# untitled.net
KiCad netlist of a schematic drawn in EAGLE
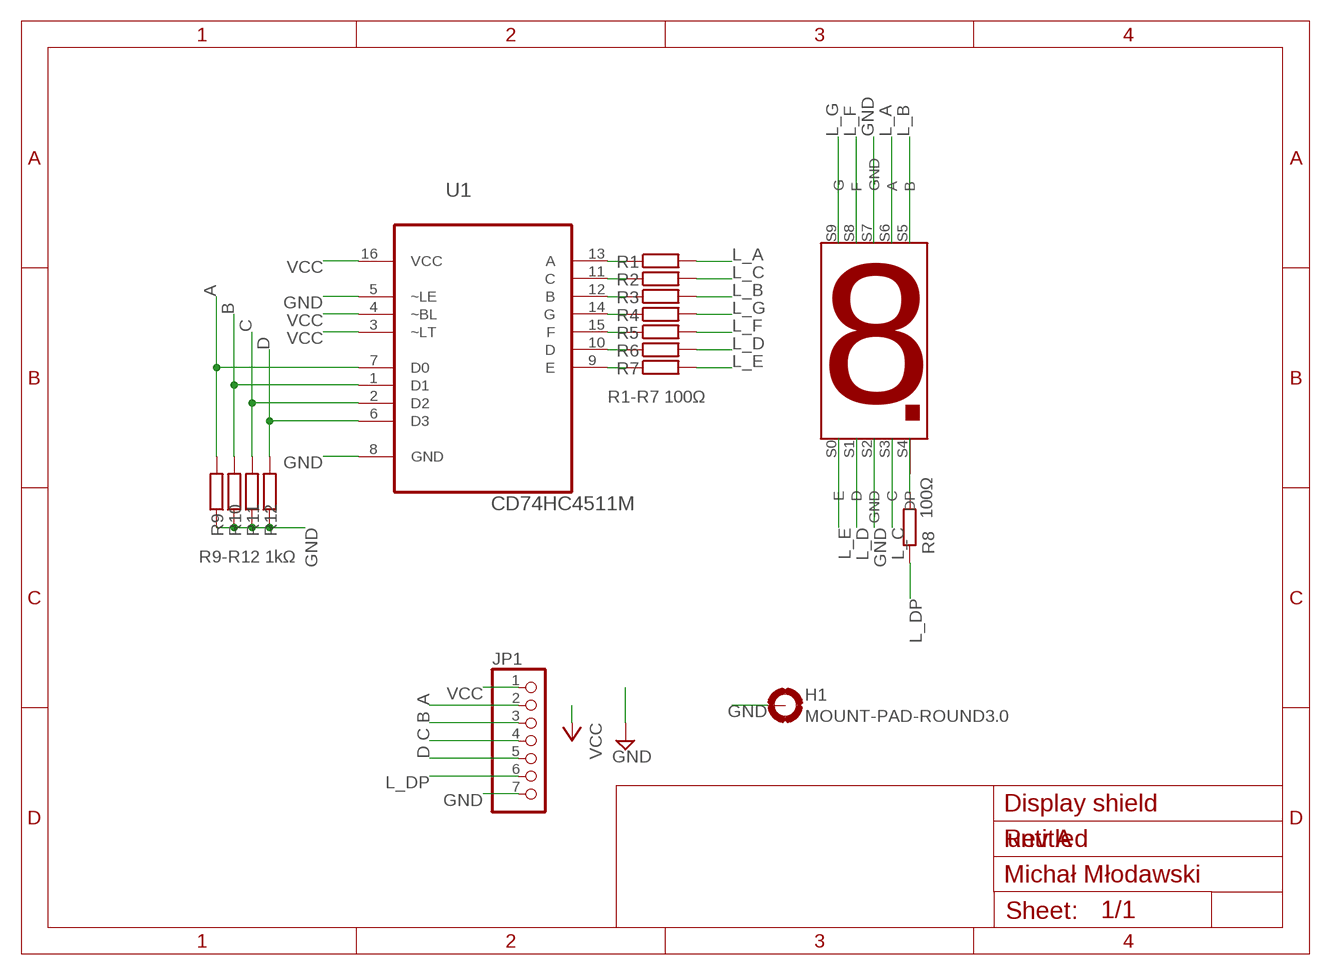
[diagram p0: schematic, sheet 1]

(export (version "E")
  (design (tool "Eeschema 10.0.6"))
  (components
    (comp (ref "H1")
      (value "MOUNT-PAD-ROUND3.0")
      (footprint "eagle-import:3,0-PAD")
      (libsource (lib "eagle-import") (part "MOUNT-PAD-ROUND3.0"))
    )
    (comp (ref "JP1")
      (value "PINHD-1X7")
      (footprint "eagle-import:1X07")
      (libsource (lib "eagle-import") (part "PINHD-1X7"))
    )
    (comp (ref "R1")
      (value "R-EU_R1206")
      (footprint "eagle-import:R1206")
      (libsource (lib "eagle-import") (part "R-EU_R1206"))
    )
    (comp (ref "R2")
      (value "R-EU_R1206")
      (footprint "eagle-import:R1206")
      (libsource (lib "eagle-import") (part "R-EU_R1206"))
    )
    (comp (ref "R3")
      (value "R-EU_R1206")
      (footprint "eagle-import:R1206")
      (libsource (lib "eagle-import") (part "R-EU_R1206"))
    )
    (comp (ref "R4")
      (value "R-EU_R1206")
      (footprint "eagle-import:R1206")
      (libsource (lib "eagle-import") (part "R-EU_R1206"))
    )
    (comp (ref "R5")
      (value "R-EU_R1206")
      (footprint "eagle-import:R1206")
      (libsource (lib "eagle-import") (part "R-EU_R1206"))
    )
    (comp (ref "R6")
      (value "R-EU_R1206")
      (footprint "eagle-import:R1206")
      (libsource (lib "eagle-import") (part "R-EU_R1206"))
    )
    (comp (ref "R7")
      (value "R-EU_R1206")
      (footprint "eagle-import:R1206")
      (libsource (lib "eagle-import") (part "R-EU_R1206"))
    )
    (comp (ref "R8")
      (value "100Ω")
      (footprint "eagle-import:R1206")
      (libsource (lib "eagle-import") (part "R-EU_R1206"))
    )
    (comp (ref "R9")
      (value "R-EU_R1206")
      (footprint "eagle-import:R1206")
      (libsource (lib "eagle-import") (part "R-EU_R1206"))
    )
    (comp (ref "R10")
      (value "R-EU_R1206")
      (footprint "eagle-import:R1206")
      (libsource (lib "eagle-import") (part "R-EU_R1206"))
    )
    (comp (ref "R11")
      (value "R-EU_R1206")
      (footprint "eagle-import:R1206")
      (libsource (lib "eagle-import") (part "R-EU_R1206"))
    )
    (comp (ref "R12")
      (value "R-EU_R1206")
      (footprint "eagle-import:R1206")
      (libsource (lib "eagle-import") (part "R-EU_R1206"))
    )
    (comp (ref "U$1")
      (value "7-SEGMENT-DISPLAY")
      (footprint "eagle-import:7-SEGMENTDISPLAY")
      (libsource (lib "eagle-import") (part "7-SEGMENT-DISPLAY"))
    )
    (comp (ref "U1")
      (value "CD74HC4511M")
      (footprint "eagle-import:SOIC127P600X175-16N")
      (fields (field (name "MF") "Texas Instruments"))
      (libsource (lib "eagle-import") (part "CD74HC4511M"))
    )
  )
  (nets
    (net (code "1") (name "/A") (class "Default")
      (node (ref "JP1") (pin "2") (pinfunction "2_2") (pintype "passive"))
      (node (ref "R9") (pin "2") (pinfunction "2_2") (pintype "passive"))
      (node (ref "U1") (pin "7") (pinfunction "D0_7") (pintype "input"))
    )
    (net (code "2") (name "/B") (class "Default")
      (node (ref "JP1") (pin "3") (pinfunction "3_3") (pintype "passive"))
      (node (ref "R10") (pin "2") (pinfunction "2_2") (pintype "passive"))
      (node (ref "U1") (pin "1") (pinfunction "D1_1") (pintype "input"))
    )
    (net (code "3") (name "/C") (class "Default")
      (node (ref "JP1") (pin "4") (pinfunction "4_4") (pintype "passive"))
      (node (ref "R11") (pin "2") (pinfunction "2_2") (pintype "passive"))
      (node (ref "U1") (pin "2") (pinfunction "D2_2") (pintype "input"))
    )
    (net (code "4") (name "/D") (class "Default")
      (node (ref "JP1") (pin "5") (pinfunction "5_5") (pintype "passive"))
      (node (ref "R12") (pin "2") (pinfunction "2_2") (pintype "passive"))
      (node (ref "U1") (pin "6") (pinfunction "D3_6") (pintype "input"))
    )
    (net (code "5") (name "/L_A") (class "Default")
      (node (ref "R1") (pin "2") (pinfunction "2_2") (pintype "passive"))
      (node (ref "U$1") (pin "S6") (pinfunction "A_S6") (pintype "input"))
    )
    (net (code "6") (name "/L_B") (class "Default")
      (node (ref "R3") (pin "2") (pinfunction "2_2") (pintype "passive"))
      (node (ref "U$1") (pin "S5") (pinfunction "B_S5") (pintype "input"))
    )
    (net (code "7") (name "/L_C") (class "Default")
      (node (ref "R2") (pin "2") (pinfunction "2_2") (pintype "passive"))
      (node (ref "U$1") (pin "S3") (pinfunction "C_S3") (pintype "input"))
    )
    (net (code "8") (name "/L_D") (class "Default")
      (node (ref "R6") (pin "2") (pinfunction "2_2") (pintype "passive"))
      (node (ref "U$1") (pin "S1") (pinfunction "D_S1") (pintype "input"))
    )
    (net (code "9") (name "/L_DP") (class "Default")
      (node (ref "JP1") (pin "6") (pinfunction "6_6") (pintype "passive"))
      (node (ref "R8") (pin "1") (pinfunction "1_1") (pintype "passive"))
    )
    (net (code "10") (name "/L_E") (class "Default")
      (node (ref "R7") (pin "2") (pinfunction "2_2") (pintype "passive"))
      (node (ref "U$1") (pin "S0") (pinfunction "E_S0") (pintype "input"))
    )
    (net (code "11") (name "/L_F") (class "Default")
      (node (ref "R5") (pin "2") (pinfunction "2_2") (pintype "passive"))
      (node (ref "U$1") (pin "S8") (pinfunction "F_S8") (pintype "input"))
    )
    (net (code "12") (name "/L_G") (class "Default")
      (node (ref "R4") (pin "2") (pinfunction "2_2") (pintype "passive"))
      (node (ref "U$1") (pin "S9") (pinfunction "G_S9") (pintype "input"))
    )
    (net (code "13") (name "GND") (class "Default")
      (node (ref "H1") (pin "B3,0") (pinfunction "MOUNT_B3,0") (pintype "passive"))
      (node (ref "JP1") (pin "7") (pinfunction "7_7") (pintype "passive"))
      (node (ref "R10") (pin "1") (pinfunction "1_1") (pintype "passive"))
      (node (ref "R11") (pin "1") (pinfunction "1_1") (pintype "passive"))
      (node (ref "R12") (pin "1") (pinfunction "1_1") (pintype "passive"))
      (node (ref "R9") (pin "1") (pinfunction "1_1") (pintype "passive"))
      (node (ref "U$1") (pin "S2") (pinfunction "GND_S2") (pintype "power_in"))
      (node (ref "U$1") (pin "S7") (pinfunction "GND_S7") (pintype "power_in"))
      (node (ref "U1") (pin "5") (pinfunction "~{LE}_5") (pintype "input"))
      (node (ref "U1") (pin "8") (pinfunction "GND_8") (pintype "passive"))
    )
    (net (code "14") (name "Net-(U$1-DP)") (class "Default")
      (node (ref "R8") (pin "2") (pinfunction "2_2") (pintype "passive"))
      (node (ref "U$1") (pin "S4") (pinfunction "DP_S4") (pintype "input"))
    )
    (net (code "15") (name "Net-(U1-A)") (class "Default")
      (node (ref "R1") (pin "1") (pinfunction "1_1") (pintype "passive"))
      (node (ref "U1") (pin "13") (pinfunction "A_13") (pintype "output"))
    )
    (net (code "16") (name "Net-(U1-B)") (class "Default")
      (node (ref "R3") (pin "1") (pinfunction "1_1") (pintype "passive"))
      (node (ref "U1") (pin "12") (pinfunction "B_12") (pintype "output"))
    )
    (net (code "17") (name "Net-(U1-C)") (class "Default")
      (node (ref "R2") (pin "1") (pinfunction "1_1") (pintype "passive"))
      (node (ref "U1") (pin "11") (pinfunction "C_11") (pintype "output"))
    )
    (net (code "18") (name "Net-(U1-D)") (class "Default")
      (node (ref "R6") (pin "1") (pinfunction "1_1") (pintype "passive"))
      (node (ref "U1") (pin "10") (pinfunction "D_10") (pintype "output"))
    )
    (net (code "19") (name "Net-(U1-E)") (class "Default")
      (node (ref "R7") (pin "1") (pinfunction "1_1") (pintype "passive"))
      (node (ref "U1") (pin "9") (pinfunction "E_9") (pintype "output"))
    )
    (net (code "20") (name "Net-(U1-F)") (class "Default")
      (node (ref "R5") (pin "1") (pinfunction "1_1") (pintype "passive"))
      (node (ref "U1") (pin "15") (pinfunction "F_15") (pintype "output"))
    )
    (net (code "21") (name "Net-(U1-G)") (class "Default")
      (node (ref "R4") (pin "1") (pinfunction "1_1") (pintype "passive"))
      (node (ref "U1") (pin "14") (pinfunction "G_14") (pintype "output"))
    )
    (net (code "22") (name "VCC") (class "Default")
      (node (ref "JP1") (pin "1") (pinfunction "1_1") (pintype "passive"))
      (node (ref "U1") (pin "16") (pinfunction "VCC_16") (pintype "power_in"))
      (node (ref "U1") (pin "3") (pinfunction "~{LT}_3") (pintype "input"))
      (node (ref "U1") (pin "4") (pinfunction "~{BL}_4") (pintype "input"))
    )
  )
)
